# writer.net
KiCad netlist of a schematic drawn in EAGLE
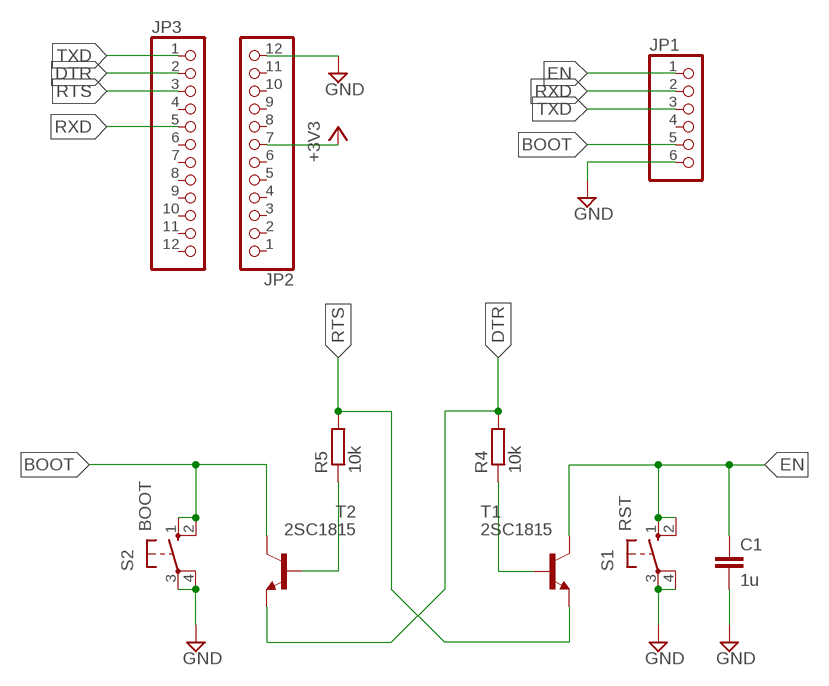
[diagram p0: schematic, sheet 1]

(export (version "E")
  (design (tool "Eeschema 10.0.6"))
  (components
    (comp (ref "C1")
      (value "1u")
      (footprint "eagle-import:C050-025X075")
      (libsource (lib "eagle-import") (part "C-EU050-025X075"))
    )
    (comp (ref "JP1")
      (value "PINHD-1X6")
      (footprint "eagle-import:1X06")
      (libsource (lib "eagle-import") (part "PINHD-1X6"))
    )
    (comp (ref "JP2")
      (value "PINHD-1X12")
      (footprint "eagle-import:1X12")
      (libsource (lib "eagle-import") (part "PINHD-1X12"))
    )
    (comp (ref "JP3")
      (value "PINHD-1X12")
      (footprint "eagle-import:1X12")
      (libsource (lib "eagle-import") (part "PINHD-1X12"))
    )
    (comp (ref "R4")
      (value "10k")
      (footprint "eagle-import:0207_10")
      (libsource (lib "eagle-import") (part "R-EU_0207/10"))
    )
    (comp (ref "R5")
      (value "10k")
      (footprint "eagle-import:0207_10")
      (libsource (lib "eagle-import") (part "R-EU_0207/10"))
    )
    (comp (ref "S1")
      (value "RST")
      (footprint "eagle-import:B3F-10XX")
      (fields (field (name "MPN") "B3F-1000"))
      (libsource (lib "eagle-import") (part "10-XX"))
    )
    (comp (ref "S2")
      (value "BOOT")
      (footprint "eagle-import:B3F-10XX")
      (fields (field (name "MPN") "B3F-1000"))
      (libsource (lib "eagle-import") (part "10-XX"))
    )
    (comp (ref "T1")
      (value "2SC1815")
      (footprint "eagle-import:TO92-ECB")
      (libsource (lib "eagle-import") (part "2SC1815"))
    )
    (comp (ref "T2")
      (value "2SC1815")
      (footprint "eagle-import:TO92-ECB")
      (libsource (lib "eagle-import") (part "2SC1815"))
    )
  )
  (nets
    (net (code "1") (name "+3V3") (class "Default")
      (node (ref "JP2") (pin "7") (pinfunction "7_7") (pintype "passive"))
    )
    (net (code "2") (name "BOOT") (class "Default")
      (node (ref "JP1") (pin "5") (pinfunction "5_5") (pintype "passive"))
      (node (ref "S2") (pin "1") (pinfunction "S_1") (pintype "passive"))
      (node (ref "S2") (pin "2") (pinfunction "S1_2") (pintype "passive"))
      (node (ref "T2") (pin "C") (pinfunction "C_C") (pintype "passive"))
    )
    (net (code "3") (name "DTR") (class "Default")
      (node (ref "JP3") (pin "2") (pinfunction "2_2") (pintype "passive"))
      (node (ref "R4") (pin "2") (pinfunction "2_2") (pintype "passive"))
      (node (ref "T2") (pin "E") (pinfunction "E_E") (pintype "passive"))
    )
    (net (code "4") (name "EN") (class "Default")
      (node (ref "C1") (pin "1") (pinfunction "1_1") (pintype "passive"))
      (node (ref "JP1") (pin "1") (pinfunction "1_1") (pintype "passive"))
      (node (ref "S1") (pin "1") (pinfunction "S_1") (pintype "passive"))
      (node (ref "S1") (pin "2") (pinfunction "S1_2") (pintype "passive"))
      (node (ref "T1") (pin "C") (pinfunction "C_C") (pintype "passive"))
    )
    (net (code "5") (name "GND") (class "Default")
      (node (ref "C1") (pin "2") (pinfunction "2_2") (pintype "passive"))
      (node (ref "JP1") (pin "6") (pinfunction "6_6") (pintype "passive"))
      (node (ref "JP2") (pin "12") (pinfunction "12_12") (pintype "passive"))
      (node (ref "S1") (pin "3") (pinfunction "P_3") (pintype "passive"))
      (node (ref "S1") (pin "4") (pinfunction "P1_4") (pintype "passive"))
      (node (ref "S2") (pin "3") (pinfunction "P_3") (pintype "passive"))
      (node (ref "S2") (pin "4") (pinfunction "P1_4") (pintype "passive"))
    )
    (net (code "6") (name "Net-(R4-Pad1)") (class "Default")
      (node (ref "R4") (pin "1") (pinfunction "1_1") (pintype "passive"))
      (node (ref "T1") (pin "B") (pinfunction "B_B") (pintype "passive"))
    )
    (net (code "7") (name "Net-(R5-Pad1)") (class "Default")
      (node (ref "R5") (pin "1") (pinfunction "1_1") (pintype "passive"))
      (node (ref "T2") (pin "B") (pinfunction "B_B") (pintype "passive"))
    )
    (net (code "8") (name "RTS") (class "Default")
      (node (ref "JP3") (pin "3") (pinfunction "3_3") (pintype "passive"))
      (node (ref "R5") (pin "2") (pinfunction "2_2") (pintype "passive"))
      (node (ref "T1") (pin "E") (pinfunction "E_E") (pintype "passive"))
    )
    (net (code "9") (name "RXD") (class "Default")
      (node (ref "JP1") (pin "2") (pinfunction "2_2") (pintype "passive"))
      (node (ref "JP3") (pin "5") (pinfunction "5_5") (pintype "passive"))
    )
    (net (code "10") (name "TXD") (class "Default")
      (node (ref "JP1") (pin "3") (pinfunction "3_3") (pintype "passive"))
      (node (ref "JP3") (pin "1") (pinfunction "1_1") (pintype "passive"))
    )
    (net (code "11") (name "unconnected-(JP1-Pad4)") (class "Default")
      (node (ref "JP1") (pin "4") (pinfunction "4_4") (pintype "passive"))
    )
    (net (code "12") (name "unconnected-(JP2-Pad1)") (class "Default")
      (node (ref "JP2") (pin "1") (pinfunction "1_1") (pintype "passive"))
    )
    (net (code "13") (name "unconnected-(JP2-Pad2)") (class "Default")
      (node (ref "JP2") (pin "2") (pinfunction "2_2") (pintype "passive"))
    )
    (net (code "14") (name "unconnected-(JP2-Pad3)") (class "Default")
      (node (ref "JP2") (pin "3") (pinfunction "3_3") (pintype "passive"))
    )
    (net (code "15") (name "unconnected-(JP2-Pad4)") (class "Default")
      (node (ref "JP2") (pin "4") (pinfunction "4_4") (pintype "passive"))
    )
    (net (code "16") (name "unconnected-(JP2-Pad5)") (class "Default")
      (node (ref "JP2") (pin "5") (pinfunction "5_5") (pintype "passive"))
    )
    (net (code "17") (name "unconnected-(JP2-Pad6)") (class "Default")
      (node (ref "JP2") (pin "6") (pinfunction "6_6") (pintype "passive"))
    )
    (net (code "18") (name "unconnected-(JP2-Pad8)") (class "Default")
      (node (ref "JP2") (pin "8") (pinfunction "8_8") (pintype "passive"))
    )
    (net (code "19") (name "unconnected-(JP2-Pad9)") (class "Default")
      (node (ref "JP2") (pin "9") (pinfunction "9_9") (pintype "passive"))
    )
    (net (code "20") (name "unconnected-(JP2-Pad10)") (class "Default")
      (node (ref "JP2") (pin "10") (pinfunction "10_10") (pintype "passive"))
    )
    (net (code "21") (name "unconnected-(JP2-Pad11)") (class "Default")
      (node (ref "JP2") (pin "11") (pinfunction "11_11") (pintype "passive"))
    )
    (net (code "22") (name "unconnected-(JP3-Pad4)") (class "Default")
      (node (ref "JP3") (pin "4") (pinfunction "4_4") (pintype "passive"))
    )
    (net (code "23") (name "unconnected-(JP3-Pad6)") (class "Default")
      (node (ref "JP3") (pin "6") (pinfunction "6_6") (pintype "passive"))
    )
    (net (code "24") (name "unconnected-(JP3-Pad7)") (class "Default")
      (node (ref "JP3") (pin "7") (pinfunction "7_7") (pintype "passive"))
    )
    (net (code "25") (name "unconnected-(JP3-Pad8)") (class "Default")
      (node (ref "JP3") (pin "8") (pinfunction "8_8") (pintype "passive"))
    )
    (net (code "26") (name "unconnected-(JP3-Pad9)") (class "Default")
      (node (ref "JP3") (pin "9") (pinfunction "9_9") (pintype "passive"))
    )
    (net (code "27") (name "unconnected-(JP3-Pad10)") (class "Default")
      (node (ref "JP3") (pin "10") (pinfunction "10_10") (pintype "passive"))
    )
    (net (code "28") (name "unconnected-(JP3-Pad11)") (class "Default")
      (node (ref "JP3") (pin "11") (pinfunction "11_11") (pintype "passive"))
    )
    (net (code "29") (name "unconnected-(JP3-Pad12)") (class "Default")
      (node (ref "JP3") (pin "12") (pinfunction "12_12") (pintype "passive"))
    )
  )
)
